# 08-TYPE-C-PORT.net
KiCad netlist of a schematic drawn in Altium Designer
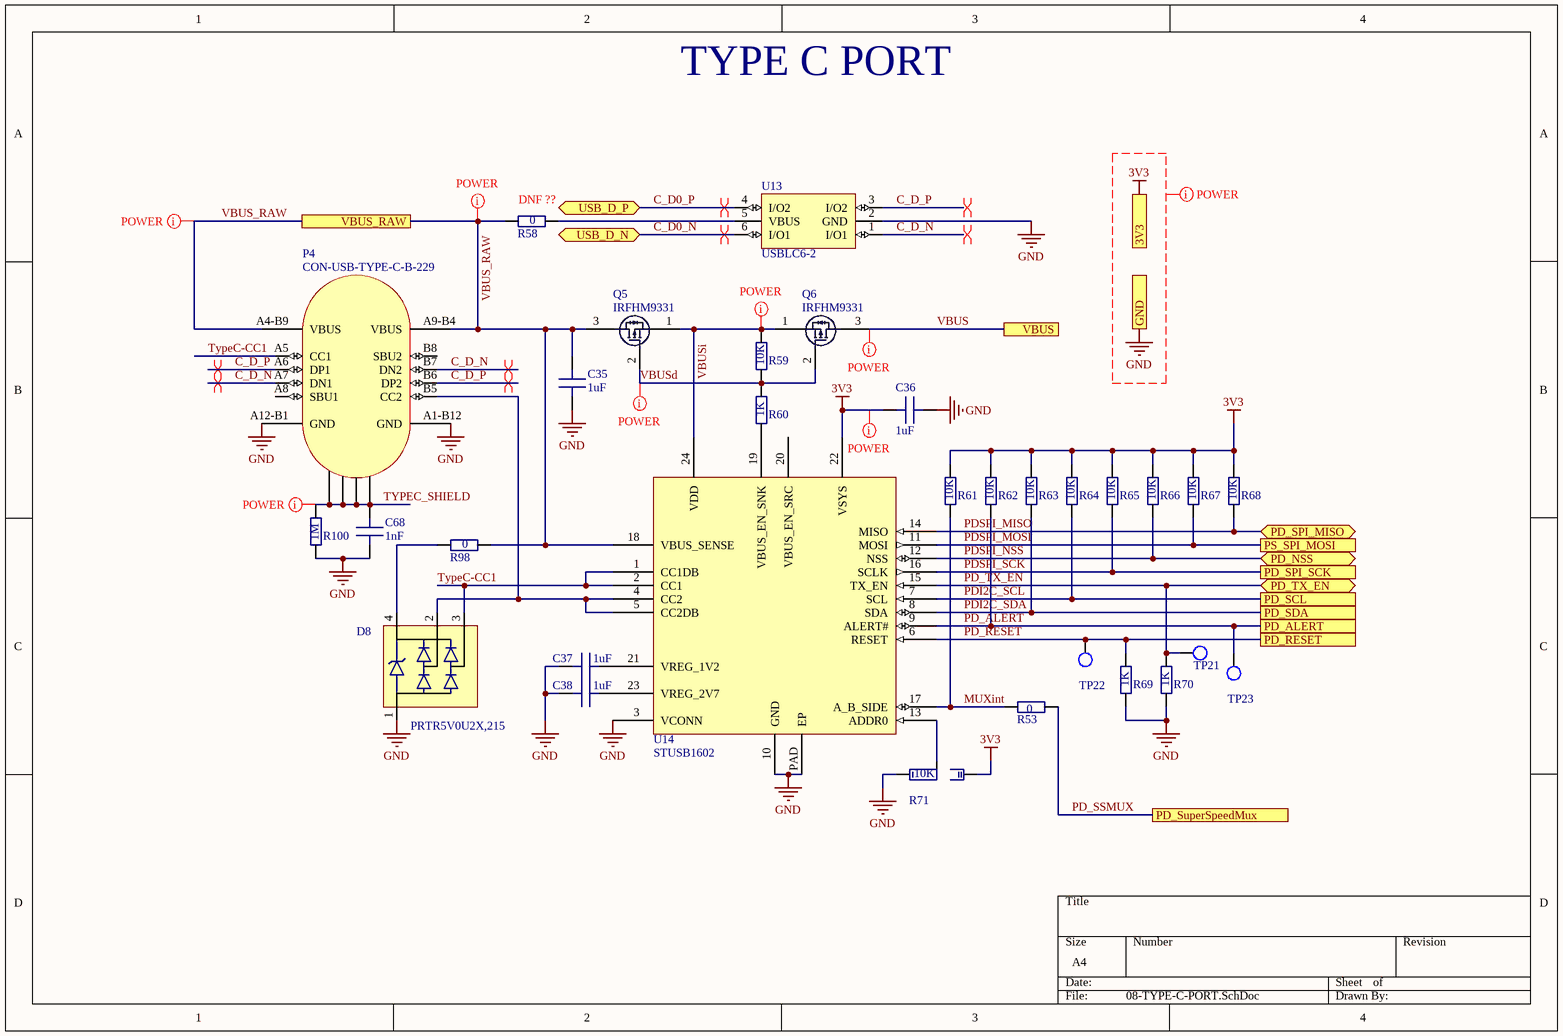
[diagram p0: 08-TYPE-C-PORT.SchDoc]

(export (version "E")
  (design (tool "Eeschema 10.0.6"))
  (components
    (comp (ref "C35")
      (value "1uF")
      (footprint "C0805")
      (description "Ceramic capacitor")
      (fields (field (name "VOLTAGE") "25V"))
      (libsource (lib "A.Shelestov_Capacitors") (part "C0805_1uF_25V"))
    )
    (comp (ref "C36")
      (value "1uF")
      (footprint "C0805")
      (description "Ceramic capacitor")
      (fields (field (name "VOLTAGE") "25V"))
      (libsource (lib "A.Shelestov_Capacitors") (part "C0805_1uF_25V"))
    )
    (comp (ref "C37")
      (value "1uF")
      (footprint "C0805")
      (description "Ceramic capacitor")
      (fields (field (name "VOLTAGE") "25V"))
      (libsource (lib "A.Shelestov_Capacitors") (part "C0805_1uF_25V"))
    )
    (comp (ref "C38")
      (value "1uF")
      (footprint "C0805")
      (description "Ceramic capacitor")
      (fields (field (name "VOLTAGE") "25V"))
      (libsource (lib "A.Shelestov_Capacitors") (part "C0805_1uF_25V"))
    )
    (comp (ref "C68")
      (value "1nF")
      (footprint "C1206")
      (description "Ceramic capacitor")
      (fields (field (name "VOLTAGE") "2KV"))
      (libsource (lib "A.Shelestov_Capacitors") (part "C1206_1nF_2KV"))
    )
    (comp (ref "D8")
      (value "PRTR5V0U2X,215")
      (footprint "SOT143B")
      (description "PRTR5V0U2X - Ultra low capacitance double rail-to-rail ESD protection diode")
      (fields (field (name "MF") "Nexperia USA"))
      (libsource (lib "ComponentsLib") (part "PRTR5V0U2X,215"))
    )
    (comp (ref "P4")
      (value "CON-USB-TYPE-C-B-229")
      (footprint "USB-Type-C-B-229")
      (description "Type C 3A Throughthole Shell, USB2 + PD SMD pins")
      (libsource (lib "ComponentsLib") (part "CON-USB-TYPE-C-B-229"))
    )
    (comp (ref "Q5")
      (value "IRFHM9331")
      (footprint "PQFN-3x3")
      (description "-30V Single P-Channel HEXFET Power MOSFET in a PQFN 3mm x 3mm package")
      (libsource (lib "ComponentsLib") (part "IRFHM9331"))
    )
    (comp (ref "Q6")
      (value "IRFHM9331")
      (footprint "PQFN-3x3")
      (description "-30V Single P-Channel HEXFET Power MOSFET in a PQFN 3mm x 3mm package")
      (libsource (lib "ComponentsLib") (part "IRFHM9331"))
    )
    (comp (ref "R53")
      (value "~")
      (footprint "R0402")
      (description "Resistor General")
      (fields (field (name "RESISTANCE") "0"))
      (libsource (lib "A.Shelestov_Resistors") (part "R0402_0R"))
    )
    (comp (ref "R58")
      (value "~")
      (footprint "R0402_NOSILK")
      (description "Resistor General")
      (fields (field (name "RESISTANCE") "0"))
      (libsource (lib "A.Shelestov_Resistors") (part "R0402_0R"))
    )
    (comp (ref "R59")
      (value "~")
      (footprint "R0603")
      (description "Resistor General")
      (fields (field (name "TOLERANCE") "1%") (field (name "RESISTANCE") "10K"))
      (libsource (lib "A.Shelestov_Resistors") (part "R0603_10K_1%"))
    )
    (comp (ref "R60")
      (value "~")
      (footprint "R0603")
      (description "Resistor General")
      (fields (field (name "TOLERANCE") "1%") (field (name "RESISTANCE") "1K"))
      (libsource (lib "A.Shelestov_Resistors") (part "R0603_1K_1%"))
    )
    (comp (ref "R61")
      (value "~")
      (footprint "R0603")
      (description "Resistor General")
      (fields (field (name "TOLERANCE") "5%") (field (name "RESISTANCE") "10K"))
      (libsource (lib "A.Shelestov_Resistors") (part "R0603_10K"))
    )
    (comp (ref "R62")
      (value "~")
      (footprint "R0603")
      (description "Resistor General")
      (fields (field (name "TOLERANCE") "5%") (field (name "RESISTANCE") "10K"))
      (libsource (lib "A.Shelestov_Resistors") (part "R0603_10K"))
    )
    (comp (ref "R63")
      (value "~")
      (footprint "R0603")
      (description "Resistor General")
      (fields (field (name "TOLERANCE") "5%") (field (name "RESISTANCE") "10K"))
      (libsource (lib "A.Shelestov_Resistors") (part "R0603_10K"))
    )
    (comp (ref "R64")
      (value "~")
      (footprint "R0603")
      (description "Resistor General")
      (fields (field (name "TOLERANCE") "5%") (field (name "RESISTANCE") "10K"))
      (libsource (lib "A.Shelestov_Resistors") (part "R0603_10K"))
    )
    (comp (ref "R65")
      (value "~")
      (footprint "R0603")
      (description "Resistor General")
      (fields (field (name "TOLERANCE") "5%") (field (name "RESISTANCE") "10K"))
      (libsource (lib "A.Shelestov_Resistors") (part "R0603_10K"))
    )
    (comp (ref "R66")
      (value "~")
      (footprint "R0603")
      (description "Resistor General")
      (fields (field (name "TOLERANCE") "5%") (field (name "RESISTANCE") "10K"))
      (libsource (lib "A.Shelestov_Resistors") (part "R0603_10K"))
    )
    (comp (ref "R67")
      (value "~")
      (footprint "R0603")
      (description "Resistor General")
      (fields (field (name "TOLERANCE") "5%") (field (name "RESISTANCE") "10K"))
      (libsource (lib "A.Shelestov_Resistors") (part "R0603_10K"))
    )
    (comp (ref "R68")
      (value "~")
      (footprint "R0603")
      (description "Resistor General")
      (fields (field (name "TOLERANCE") "5%") (field (name "RESISTANCE") "10K"))
      (libsource (lib "A.Shelestov_Resistors") (part "R0603_10K"))
    )
    (comp (ref "R69")
      (value "~")
      (footprint "R0603")
      (description "Resistor General")
      (fields (field (name "TOLERANCE") "5%") (field (name "RESISTANCE") "1K"))
      (libsource (lib "A.Shelestov_Resistors") (part "R0603_1K"))
    )
    (comp (ref "R70")
      (value "~")
      (footprint "R0603")
      (description "Resistor General")
      (fields (field (name "TOLERANCE") "5%") (field (name "RESISTANCE") "1K"))
      (libsource (lib "A.Shelestov_Resistors") (part "R0603_1K"))
    )
    (comp (ref "R71")
      (value "~")
      (footprint "RJ0603")
      (description "Resistor General")
      (fields (field (name "TOLERANCE") "5%") (field (name "RESISTANCE") "10K"))
      (libsource (lib "A.Shelestov_Resistors") (part "RJ0603_10K"))
    )
    (comp (ref "R98")
      (value "~")
      (footprint "R0402")
      (description "Resistor General")
      (fields (field (name "RESISTANCE") "0"))
      (libsource (lib "A.Shelestov_Resistors") (part "R0402_0R"))
    )
    (comp (ref "R100")
      (value "~")
      (footprint "R2512")
      (description "Resistor General")
      (fields (field (name "TOLERANCE") "5%") (field (name "RESISTANCE") "1M"))
      (libsource (lib "A.Shelestov_Resistors") (part "R2512_1M_5%"))
    )
    (comp (ref "TP21")
      (value "TEST_POINT")
      (footprint "TP_1mm")
      (libsource (lib "ComponentsLib") (part "TEST_POINT"))
    )
    (comp (ref "TP22")
      (value "TEST_POINT")
      (footprint "TP_1mm")
      (libsource (lib "ComponentsLib") (part "TEST_POINT"))
    )
    (comp (ref "TP23")
      (value "TEST_POINT")
      (footprint "TP_1mm")
      (libsource (lib "ComponentsLib") (part "TEST_POINT"))
    )
    (comp (ref "U13")
      (value "USBLC6-2")
      (footprint "SOT-666")
      (description "Very low capacitance ESD protection")
      (libsource (lib "ComponentsLib") (part "USBLC6-2"))
    )
    (comp (ref "U14")
      (value "STUSB1602")
      (footprint "QFN24-4x4x0.9")
      (description "USB Type-C controller with TX/RX line driver and BMC")
      (libsource (lib "ComponentsLib") (part "STUSB1602"))
    )
  )
  (nets
    (net (code "1") (name "/C_D0_N") (class "Default")
      (node (ref "U13") (pin "6") (pinfunction "I/O1_6") (pintype "bidirectional"))
    )
    (net (code "2") (name "/C_D0_P") (class "Default")
      (node (ref "U13") (pin "4") (pinfunction "I/O2_4") (pintype "bidirectional"))
    )
    (net (code "3") (name "/C_D_N") (class "Default")
      (node (ref "P4") (pin "A7") (pinfunction "DN1_A7") (pintype "bidirectional"))
      (node (ref "P4") (pin "B7") (pinfunction "DN2_B7") (pintype "bidirectional"))
      (node (ref "U13") (pin "1") (pinfunction "I/O1_1") (pintype "bidirectional"))
    )
    (net (code "4") (name "/C_D_P") (class "Default")
      (node (ref "P4") (pin "A6") (pinfunction "DP1_A6") (pintype "bidirectional"))
      (node (ref "P4") (pin "B6") (pinfunction "DP2_B6") (pintype "bidirectional"))
      (node (ref "U13") (pin "3") (pinfunction "I/O2_3") (pintype "bidirectional"))
    )
    (net (code "5") (name "/MUXint") (class "Default")
      (node (ref "R53") (pin "2") (pinfunction "2_2") (pintype "passive"))
      (node (ref "R61") (pin "1") (pinfunction "1_1") (pintype "passive"))
      (node (ref "U14") (pin "17") (pinfunction "A_B_SIDE_17") (pintype "bidirectional"))
    )
    (net (code "6") (name "/PDI2C_SCL") (class "Default")
      (node (ref "R64") (pin "1") (pinfunction "1_1") (pintype "passive"))
      (node (ref "U14") (pin "7") (pinfunction "SCL_7") (pintype "input"))
    )
    (net (code "7") (name "/PDI2C_SDA") (class "Default")
      (node (ref "R63") (pin "1") (pinfunction "1_1") (pintype "passive"))
      (node (ref "U14") (pin "8") (pinfunction "SDA_8") (pintype "bidirectional"))
    )
    (net (code "8") (name "/PDSPI_MISO") (class "Default")
      (node (ref "R68") (pin "1") (pinfunction "1_1") (pintype "passive"))
      (node (ref "U14") (pin "14") (pinfunction "MISO_14") (pintype "input"))
    )
    (net (code "9") (name "/PDSPI_MOSI") (class "Default")
      (node (ref "R67") (pin "1") (pinfunction "1_1") (pintype "passive"))
      (node (ref "U14") (pin "11") (pinfunction "MOSI_11") (pintype "output"))
    )
    (net (code "10") (name "/PDSPI_NSS") (class "Default")
      (node (ref "R66") (pin "1") (pinfunction "1_1") (pintype "passive"))
      (node (ref "U14") (pin "12") (pinfunction "NSS_12") (pintype "bidirectional"))
    )
    (net (code "11") (name "/PDSPI_SCK") (class "Default")
      (node (ref "R65") (pin "1") (pinfunction "1_1") (pintype "passive"))
      (node (ref "U14") (pin "16") (pinfunction "SCLK_16") (pintype "output"))
    )
    (net (code "12") (name "/PD_ALERT") (class "Default")
      (node (ref "R62") (pin "1") (pinfunction "1_1") (pintype "passive"))
      (node (ref "TP23") (pin "1") (pinfunction "1_1") (pintype "passive"))
      (node (ref "U14") (pin "9") (pinfunction "ALERT#_9") (pintype "bidirectional"))
    )
    (net (code "13") (name "/PD_RESET") (class "Default")
      (node (ref "R69") (pin "2") (pinfunction "2_2") (pintype "passive"))
      (node (ref "TP22") (pin "1") (pinfunction "1_1") (pintype "passive"))
      (node (ref "U14") (pin "6") (pinfunction "RESET_6") (pintype "input"))
    )
    (net (code "14") (name "/PD_SSMUX") (class "Default")
      (node (ref "R53") (pin "1") (pinfunction "1_1") (pintype "passive"))
    )
    (net (code "15") (name "/PD_TX_EN") (class "Default")
      (node (ref "R70") (pin "2") (pinfunction "2_2") (pintype "passive"))
      (node (ref "TP21") (pin "1") (pinfunction "1_1") (pintype "passive"))
      (node (ref "U14") (pin "15") (pinfunction "TX_EN_15") (pintype "input"))
    )
    (net (code "16") (name "/TYPEC_SHIELD") (class "Default")
      (node (ref "C68") (pin "2") (pinfunction "2_2") (pintype "passive"))
      (node (ref "P4") (pin "SHIELD") (pinfunction "SHIELD_SHIELD") (pintype "power_in"))
      (node (ref "R100") (pin "2") (pinfunction "2_2") (pintype "passive"))
    )
    (net (code "17") (name "/TypeC-CC1") (class "Default")
      (node (ref "D8") (pin "3") (pinfunction "P$3_3") (pintype "passive"))
      (node (ref "P4") (pin "A5") (pinfunction "CC1_A5") (pintype "bidirectional"))
      (node (ref "U14") (pin "1") (pinfunction "CC1DB_1") (pintype "power_in"))
      (node (ref "U14") (pin "2") (pinfunction "CC1_2") (pintype "power_in"))
    )
    (net (code "18") (name "/VBUS") (class "Default")
      (node (ref "Q6") (pin "3") (pinfunction "D_3") (pintype "passive"))
    )
    (net (code "19") (name "/VBUS_RAW") (class "Default")
      (node (ref "C35") (pin "2") (pinfunction "2_2") (pintype "passive"))
      (node (ref "P4") (pin "A4-B9") (pinfunction "VBUS_A4-B9") (pintype "power_in"))
      (node (ref "P4") (pin "A9-B4") (pinfunction "VBUS_A9-B4") (pintype "power_in"))
      (node (ref "Q5") (pin "3") (pinfunction "D_3") (pintype "passive"))
      (node (ref "R58") (pin "1") (pinfunction "1_1") (pintype "passive"))
      (node (ref "R98") (pin "2") (pinfunction "2_2") (pintype "passive"))
      (node (ref "U14") (pin "18") (pinfunction "VBUS_SENSE_18") (pintype "power_in"))
    )
    (net (code "20") (name "/VBUSd") (class "Default")
      (node (ref "Q5") (pin "2") (pinfunction "G_2") (pintype "passive"))
      (node (ref "Q6") (pin "2") (pinfunction "G_2") (pintype "passive"))
      (node (ref "R59") (pin "1") (pinfunction "1_1") (pintype "passive"))
      (node (ref "R60") (pin "2") (pinfunction "2_2") (pintype "passive"))
    )
    (net (code "21") (name "/VBUSi") (class "Default")
      (node (ref "Q5") (pin "1") (pinfunction "S_1") (pintype "passive"))
      (node (ref "Q6") (pin "1") (pinfunction "S_1") (pintype "passive"))
      (node (ref "R59") (pin "2") (pinfunction "2_2") (pintype "passive"))
      (node (ref "U14") (pin "24") (pinfunction "VDD_24") (pintype "power_in"))
    )
    (net (code "22") (name "3V3") (class "Default")
      (node (ref "C36") (pin "1") (pinfunction "1_1") (pintype "passive"))
      (node (ref "R61") (pin "2") (pinfunction "2_2") (pintype "passive"))
      (node (ref "R62") (pin "2") (pinfunction "2_2") (pintype "passive"))
      (node (ref "R63") (pin "2") (pinfunction "2_2") (pintype "passive"))
      (node (ref "R64") (pin "2") (pinfunction "2_2") (pintype "passive"))
      (node (ref "R65") (pin "2") (pinfunction "2_2") (pintype "passive"))
      (node (ref "R66") (pin "2") (pinfunction "2_2") (pintype "passive"))
      (node (ref "R67") (pin "2") (pinfunction "2_2") (pintype "passive"))
      (node (ref "R68") (pin "2") (pinfunction "2_2") (pintype "passive"))
      (node (ref "R71") (pin "3") (pinfunction "3_3") (pintype "passive"))
      (node (ref "U14") (pin "22") (pinfunction "VSYS_22") (pintype "power_in"))
    )
    (net (code "23") (name "GND") (class "Default")
      (node (ref "C35") (pin "1") (pinfunction "1_1") (pintype "passive"))
      (node (ref "C36") (pin "2") (pinfunction "2_2") (pintype "passive"))
      (node (ref "C37") (pin "1") (pinfunction "1_1") (pintype "passive"))
      (node (ref "C38") (pin "1") (pinfunction "1_1") (pintype "passive"))
      (node (ref "C68") (pin "1") (pinfunction "1_1") (pintype "passive"))
      (node (ref "D8") (pin "1") (pinfunction "P$1_1") (pintype "passive"))
      (node (ref "P4") (pin "A1-B12") (pinfunction "GND_A1-B12") (pintype "power_in"))
      (node (ref "P4") (pin "A12-B1") (pinfunction "GND_A12-B1") (pintype "power_in"))
      (node (ref "R100") (pin "1") (pinfunction "1_1") (pintype "passive"))
      (node (ref "R69") (pin "1") (pinfunction "1_1") (pintype "passive"))
      (node (ref "R70") (pin "1") (pinfunction "1_1") (pintype "passive"))
      (node (ref "R71") (pin "1") (pinfunction "1_1") (pintype "passive"))
      (node (ref "U13") (pin "2") (pinfunction "GND_2") (pintype "power_in"))
      (node (ref "U14") (pin "10") (pinfunction "GND_10") (pintype "power_in"))
      (node (ref "U14") (pin "3") (pinfunction "VCONN_3") (pintype "power_in"))
      (node (ref "U14") (pin "PAD") (pinfunction "EP_PAD") (pintype "power_in"))
    )
    (net (code "24") (name "Net-(D8-P$2)") (class "Default")
      (node (ref "D8") (pin "2") (pinfunction "P$2_2") (pintype "passive"))
      (node (ref "P4") (pin "B5") (pinfunction "CC2_B5") (pintype "bidirectional"))
      (node (ref "U14") (pin "4") (pinfunction "CC2_4") (pintype "power_in"))
      (node (ref "U14") (pin "5") (pinfunction "CC2DB_5") (pintype "power_in"))
    )
    (net (code "25") (name "Net-(D8-P$4)") (class "Default")
      (node (ref "D8") (pin "4") (pinfunction "P$4_4") (pintype "passive"))
      (node (ref "R98") (pin "1") (pinfunction "1_1") (pintype "passive"))
    )
    (net (code "26") (name "Net-(U13-VBUS)") (class "Default")
      (node (ref "R58") (pin "2") (pinfunction "2_2") (pintype "passive"))
      (node (ref "U13") (pin "5") (pinfunction "VBUS_5") (pintype "power_in"))
    )
    (net (code "27") (name "Net-(U14-ADDR0)") (class "Default")
      (node (ref "R71") (pin "2") (pinfunction "2_2") (pintype "passive"))
      (node (ref "U14") (pin "13") (pinfunction "ADDR0_13") (pintype "input"))
    )
    (net (code "28") (name "Net-(U14-VBUS_EN_SNK)") (class "Default")
      (node (ref "R60") (pin "1") (pinfunction "1_1") (pintype "passive"))
      (node (ref "U14") (pin "19") (pinfunction "VBUS_EN_SNK_19") (pintype "power_in"))
    )
    (net (code "29") (name "Net-(U14-VREG_1V2)") (class "Default")
      (node (ref "C37") (pin "2") (pinfunction "2_2") (pintype "passive"))
      (node (ref "U14") (pin "21") (pinfunction "VREG_1V2_21") (pintype "power_in"))
    )
    (net (code "30") (name "Net-(U14-VREG_2V7)") (class "Default")
      (node (ref "C38") (pin "2") (pinfunction "2_2") (pintype "passive"))
      (node (ref "U14") (pin "23") (pinfunction "VREG_2V7_23") (pintype "power_in"))
    )
    (net (code "31") (name "unconnected-(P4-SBU1-PadA8)") (class "Default")
      (node (ref "P4") (pin "A8") (pinfunction "SBU1_A8") (pintype "bidirectional"))
    )
    (net (code "32") (name "unconnected-(P4-SBU2-PadB8)") (class "Default")
      (node (ref "P4") (pin "B8") (pinfunction "SBU2_B8") (pintype "bidirectional"))
    )
    (net (code "33") (name "unconnected-(U14-VBUS_EN_SRC-Pad20)") (class "Default")
      (node (ref "U14") (pin "20") (pinfunction "VBUS_EN_SRC_20") (pintype "power_in"))
    )
  )
)
